# FOC_Drive.net
KiCad netlist of a schematic drawn in Altium Designer
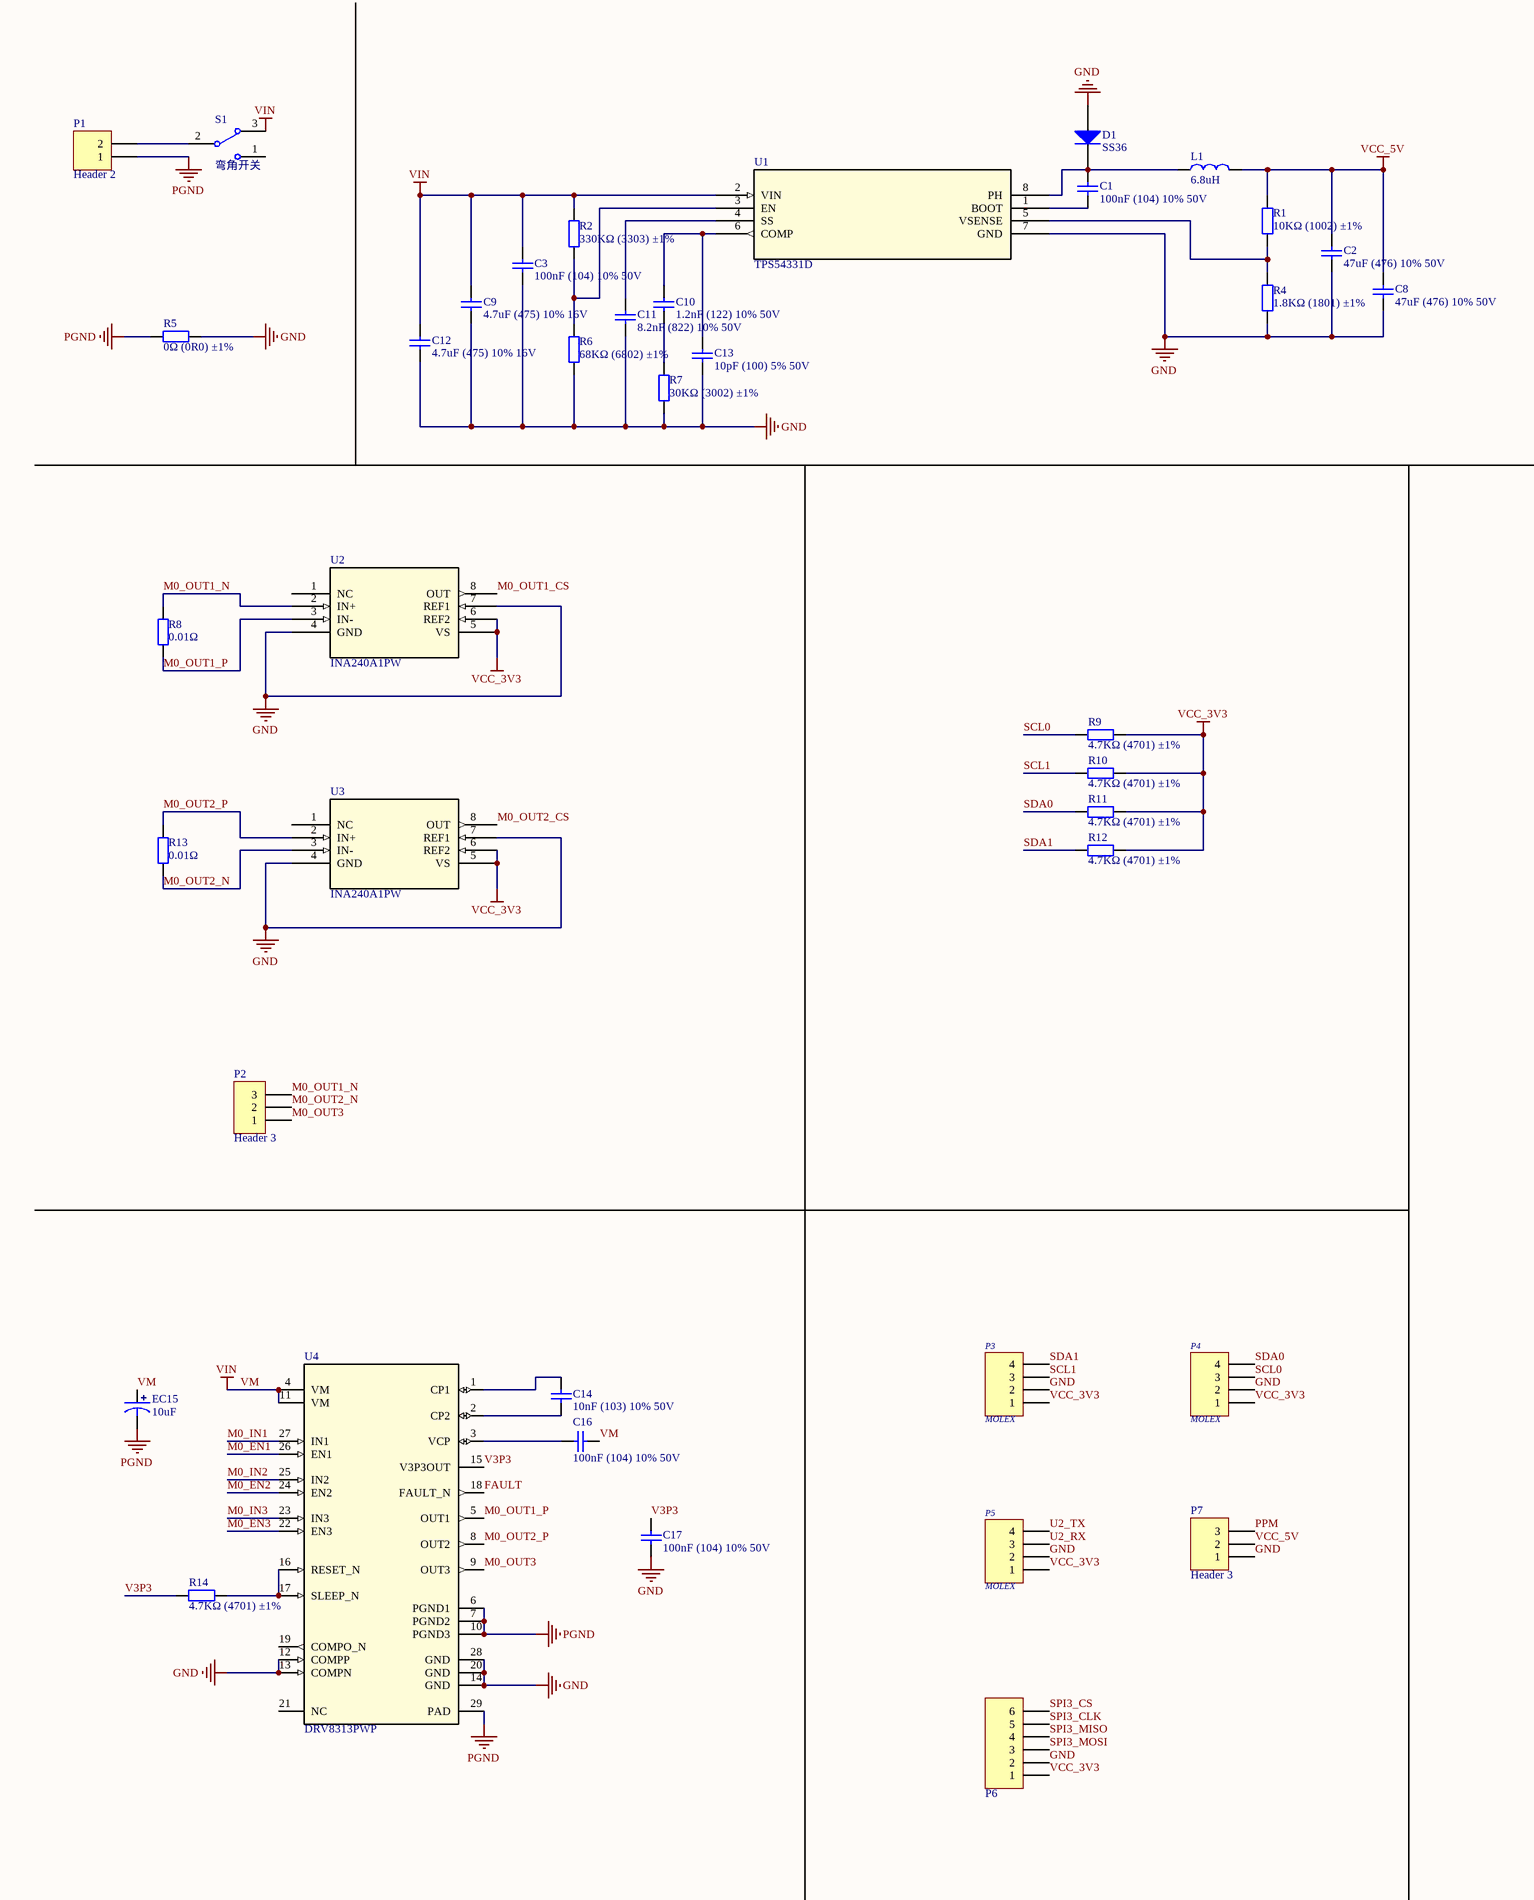
[diagram p0: FOC Drive.SchDoc, left]
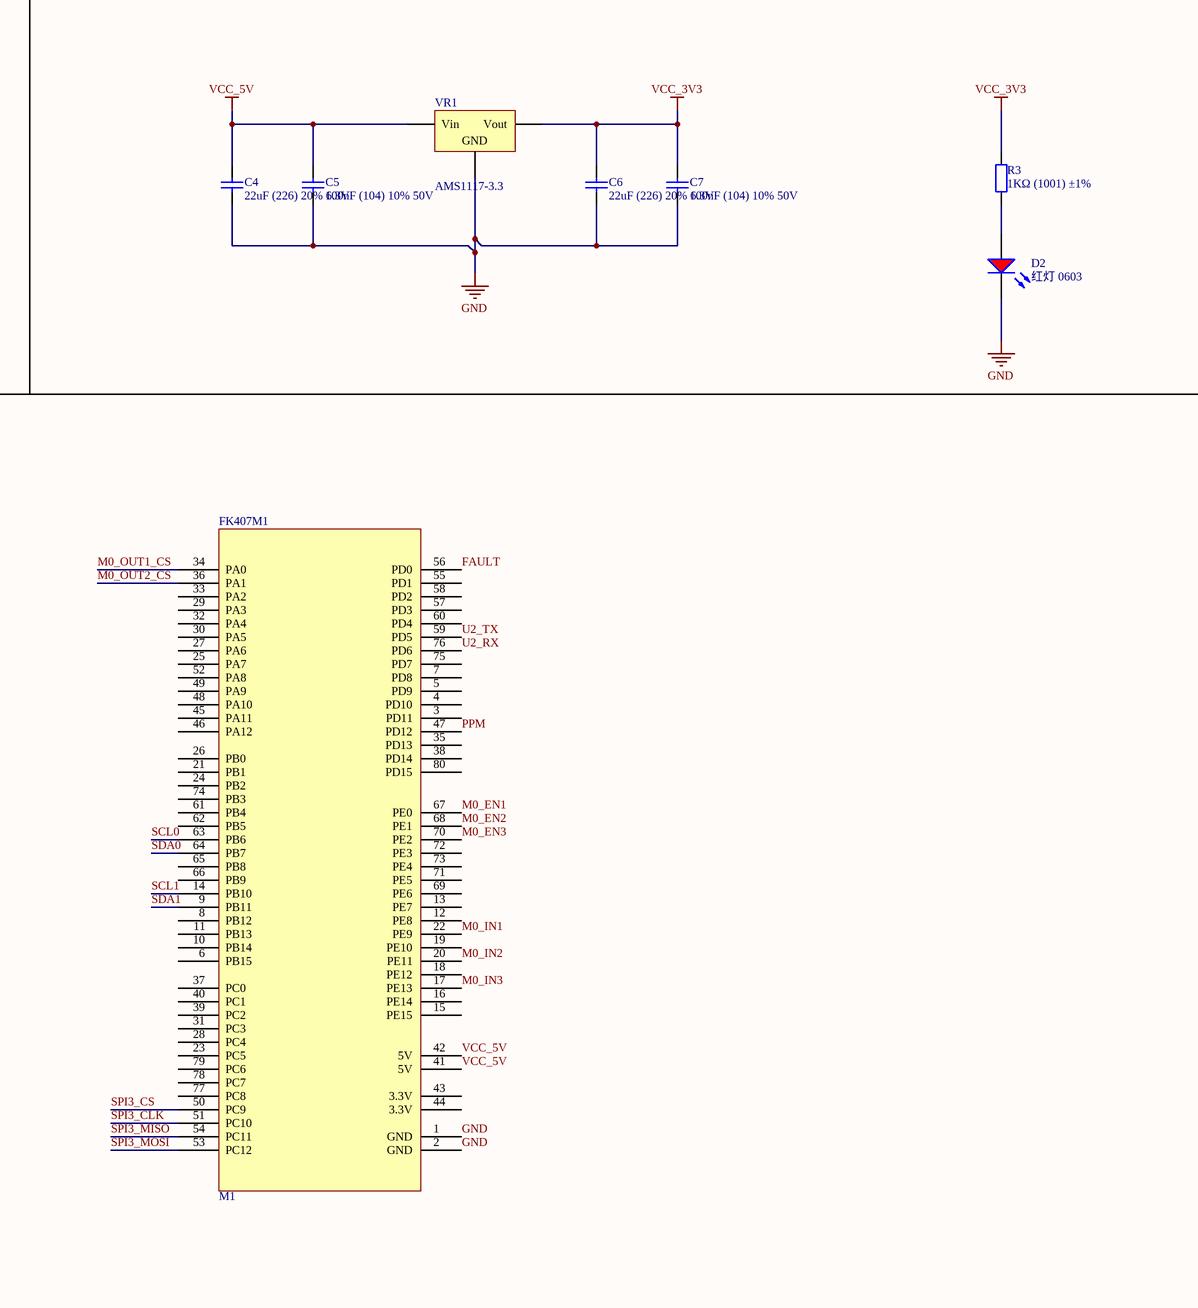
[diagram p1: FOC Drive.SchDoc, right]

(export (version "E")
  (design (tool "Eeschema 10.0.6"))
  (components
    (comp (ref "C1")
      (value "100nF (104) 10% 50V")
      (footprint "0603_C")
      (description "贴片电容")
      (libsource (lib "Miscellaneous Devices LC") (part "0603 100nF (104) 10% 50V"))
    )
    (comp (ref "C2")
      (value "47uF (476) 10% 50V")
      (footprint "0603_C")
      (description "贴片电容")
      (libsource (lib "Miscellaneous Devices LC") (part "0603 47nF (473) 10% 50V"))
    )
    (comp (ref "C3")
      (value "100nF (104) 10% 50V")
      (footprint "0603_C")
      (description "贴片电容")
      (libsource (lib "Miscellaneous Devices LC") (part "0603 100nF (104) 10% 50V"))
    )
    (comp (ref "C4")
      (value "22uF (226) 20% 6.3V")
      (footprint "0603_C")
      (description "贴片电容")
      (libsource (lib "Miscellaneous Devices LC") (part "0603 22uF (226) 20% 6.3V"))
    )
    (comp (ref "C5")
      (value "100nF (104) 10% 50V")
      (footprint "0603_C")
      (description "贴片电容")
      (libsource (lib "Miscellaneous Devices LC") (part "0603 100nF (104) 10% 50V"))
    )
    (comp (ref "C6")
      (value "22uF (226) 20% 6.3V")
      (footprint "0603_C")
      (description "贴片电容")
      (libsource (lib "Miscellaneous Devices LC") (part "0603 22uF (226) 20% 6.3V"))
    )
    (comp (ref "C7")
      (value "100nF (104) 10% 50V")
      (footprint "0603_C")
      (description "贴片电容")
      (libsource (lib "Miscellaneous Devices LC") (part "0603 100nF (104) 10% 50V"))
    )
    (comp (ref "C8")
      (value "47uF (476) 10% 50V")
      (footprint "0603_C")
      (description "贴片电容")
      (libsource (lib "Miscellaneous Devices LC") (part "0603 47nF (473) 10% 50V"))
    )
    (comp (ref "C9")
      (value "4.7uF (475) 10% 16V")
      (footprint "0603_C")
      (description "贴片电容")
      (libsource (lib "Miscellaneous Devices LC") (part "0603 4.7uF (475) 10% 16V"))
    )
    (comp (ref "C10")
      (value "1.2nF (122) 10% 50V")
      (footprint "0603_C")
      (description "贴片电容")
      (libsource (lib "Miscellaneous Devices LC") (part "0603 1.2nF (122) 10% 50V"))
    )
    (comp (ref "C11")
      (value "8.2nF (822) 10% 50V")
      (footprint "0603_C")
      (description "贴片电容")
      (libsource (lib "Miscellaneous Devices LC") (part "0603 8.2nF (822) 10% 50V"))
    )
    (comp (ref "C12")
      (value "4.7uF (475) 10% 16V")
      (footprint "0603_C")
      (description "贴片电容")
      (libsource (lib "Miscellaneous Devices LC") (part "0603 4.7uF (475) 10% 16V"))
    )
    (comp (ref "C13")
      (value "10pF (100) 5% 50V")
      (footprint "0603_C")
      (description "贴片电容")
      (libsource (lib "Miscellaneous Devices LC") (part "0603 10pF (100) 5% 50V"))
    )
    (comp (ref "C14")
      (value "10nF (103) 10% 50V")
      (footprint "0603_C")
      (description "贴片电容")
      (libsource (lib "Miscellaneous Devices LC") (part "0603 10nF (103) 10% 50V"))
    )
    (comp (ref "C16")
      (value "100nF (104) 10% 50V")
      (footprint "0603_C")
      (description "贴片电容")
      (libsource (lib "Miscellaneous Devices LC") (part "0603 100nF (104) 10% 50V"))
    )
    (comp (ref "C17")
      (value "100nF (104) 10% 50V")
      (footprint "0603_C")
      (description "贴片电容")
      (libsource (lib "Miscellaneous Devices LC") (part "0603 100nF (104) 10% 50V"))
    )
    (comp (ref "D1")
      (value "SS36")
      (footprint "SMA(DO-214AC)_S5")
      (description "二极管")
      (libsource (lib "Miscellaneous Customized Items") (part "SMA(DO-214AC) US1M"))
    )
    (comp (ref "D2")
      (value "红灯 0603")
      (footprint "0603_LED_S1")
      (description "发光二极管")
      (libsource (lib "Miscellaneous Devices LC") (part "0603 红灯"))
    )
    (comp (ref "EC15")
      (value "10uF")
      (footprint "SMD-EC5.0X5.3X5.4")
      (description "贴片电解电容")
      (libsource (lib "电容") (part "SMD_ECAP"))
    )
    (comp (ref "FK407M1")
      (value "M1")
      (footprint "FK407M1")
      (libsource (lib "Miscellaneous Customized Items") (part "FK407M1"))
    )
    (comp (ref "L1")
      (value "6.8uH")
      (footprint "IND-SMD_L5.0-W5.0_SWPA5040S")
      (description "5040")
      (libsource (lib "Miscellaneous Customized Items") (part "L"))
    )
    (comp (ref "P1")
      (value "Header 2")
      (footprint "KF127-2P-5mm")
      (description "Header, 2-Pin")
      (fields (field (name "PUBLISHER") "Altium Limited"))
      (libsource (lib "Miscellaneous Customized Items") (part "Header 2 5mm"))
    )
    (comp (ref "P2")
      (value "Header 3")
      (footprint "KF127-3P-5mm")
      (description "Header, 3-Pin")
      (fields (field (name "PUBLISHER") "Altium Limited"))
      (libsource (lib "Miscellaneous Customized Items") (part "Header 3"))
    )
    (comp (ref "P3")
      (value "MOLEX")
      (footprint "SH1.0-4P-L")
      (fields (field (name "PUBLISHER") "Altium Limited"))
      (libsource (lib "TM4C_Series") (part "SH_4P"))
    )
    (comp (ref "P4")
      (value "MOLEX")
      (footprint "SH1.0-4P-L")
      (fields (field (name "PUBLISHER") "Altium Limited"))
      (libsource (lib "TM4C_Series") (part "SH_4P"))
    )
    (comp (ref "P5")
      (value "MOLEX")
      (footprint "SH1.0-4P-L")
      (fields (field (name "PUBLISHER") "Altium Limited"))
      (libsource (lib "TM4C_Series") (part "SH_4P"))
    )
    (comp (ref "P6")
      (value "SH_6P")
      (footprint "SH1.0-6P-L")
      (description "Header, 6-Pin")
      (fields (field (name "PUBLISHER") "Altium Limited"))
      (libsource (lib "TM4C_Series") (part "SH_6P"))
    )
    (comp (ref "P7")
      (value "Header 3")
      (footprint "HDR1X3")
      (description "Header, 3-Pin")
      (fields (field (name "PUBLISHER") "Altium Limited"))
      (libsource (lib "Miscellaneous Connectors") (part "Header 3"))
    )
    (comp (ref "R1")
      (value "10KΩ (1002) ±1%")
      (footprint "0603_R")
      (description "贴片电阻")
      (libsource (lib "Miscellaneous Devices LC") (part "0603 10KΩ (1002) 1%"))
    )
    (comp (ref "R2")
      (value "330KΩ (3303) ±1%")
      (footprint "0603_R")
      (description "贴片电阻")
      (libsource (lib "Miscellaneous Devices LC") (part "0603 330KΩ (3303) 1%"))
    )
    (comp (ref "R3")
      (value "1KΩ (1001) ±1%")
      (footprint "0603_R")
      (description "贴片电阻")
      (libsource (lib "Miscellaneous Devices LC") (part "0603 1KΩ (1001) 1%"))
    )
    (comp (ref "R4")
      (value "1.8KΩ (1801) ±1%")
      (footprint "0603_R")
      (description "贴片电阻")
      (libsource (lib "Miscellaneous Devices LC") (part "0603 1.8KΩ (1801) 1%"))
    )
    (comp (ref "R5")
      (value "0Ω (0R0) ±1%")
      (footprint "0805_R")
      (description "贴片电阻")
      (libsource (lib "Miscellaneous Devices LC") (part "0805 0Ω (0R0) 1%"))
    )
    (comp (ref "R6")
      (value "68KΩ (6802) ±1%")
      (footprint "0603_R")
      (description "贴片电阻")
      (libsource (lib "Miscellaneous Devices LC") (part "0603 68KΩ (6802) 1%"))
    )
    (comp (ref "R7")
      (value "30KΩ (3002) ±1%")
      (footprint "0603_R")
      (description "贴片电阻")
      (libsource (lib "Miscellaneous Devices LC") (part "0603 30KΩ (3002) 1%"))
    )
    (comp (ref "R8")
      (value "0.01Ω")
      (footprint "1206_R")
      (description "贴片电阻")
      (libsource (lib "Miscellaneous Devices LC") (part "1206 0Ω (0R0) 1%"))
    )
    (comp (ref "R9")
      (value "4.7KΩ (4701) ±1%")
      (footprint "0603_R")
      (description "贴片电阻")
      (libsource (lib "Miscellaneous Devices LC") (part "0603 4.7KΩ (4701) 1%"))
    )
    (comp (ref "R10")
      (value "4.7KΩ (4701) ±1%")
      (footprint "0603_R")
      (description "贴片电阻")
      (libsource (lib "Miscellaneous Devices LC") (part "0603 4.7KΩ (4701) 1%"))
    )
    (comp (ref "R11")
      (value "4.7KΩ (4701) ±1%")
      (footprint "0603_R")
      (description "贴片电阻")
      (libsource (lib "Miscellaneous Devices LC") (part "0603 4.7KΩ (4701) 1%"))
    )
    (comp (ref "R12")
      (value "4.7KΩ (4701) ±1%")
      (footprint "0603_R")
      (description "贴片电阻")
      (libsource (lib "Miscellaneous Devices LC") (part "0603 4.7KΩ (4701) 1%"))
    )
    (comp (ref "R13")
      (value "0.01Ω")
      (footprint "1206_R")
      (description "贴片电阻")
      (libsource (lib "Miscellaneous Devices LC") (part "1206 0Ω (0R0) 1%"))
    )
    (comp (ref "R14")
      (value "4.7KΩ (4701) ±1%")
      (footprint "0603_R")
      (description "贴片电阻")
      (libsource (lib "Miscellaneous Devices LC") (part "0603 4.7KΩ (4701) 1%"))
    )
    (comp (ref "S1")
      (value "弯角开关")
      (footprint "SS-12F23")
      (libsource (lib "Miscellaneous Customized Items") (part "SS-12F23"))
    )
    (comp (ref "U1")
      (value "TPS54331D")
      (footprint "D8-M")
      (description "No Description Available")
      (fields (field (name "COPYRIGHT") "Copyright (C) 2022 Ultra Librarian. All rights reserved."))
      (libsource (lib "Miscellaneous Customized Items") (part "TPS54331D"))
    )
    (comp (ref "U2")
      (value "INA240A1PW")
      (footprint "PW0008A_N_TEX")
      (description "No Description Available")
      (fields (field (name "COPYRIGHT") "Copyright (C) 2022 Ultra Librarian. All rights reserved."))
      (libsource (lib "Miscellaneous Customized Items") (part "INA240A1PW"))
    )
    (comp (ref "U3")
      (value "INA240A1PW")
      (footprint "PW0008A_N_TEX")
      (description "No Description Available")
      (fields (field (name "COPYRIGHT") "Copyright (C) 2022 Ultra Librarian. All rights reserved."))
      (libsource (lib "Miscellaneous Customized Items") (part "INA240A1PW"))
    )
    (comp (ref "U4")
      (value "DRV8313PWP")
      (footprint "PWP0028F_N")
      (description "No Description Available")
      (fields (field (name "COPYRIGHT") "Copyright (C) 2022 Ultra Librarian. All rights reserved."))
      (libsource (lib "Miscellaneous Customized Items") (part "DRV8313PWP"))
    )
    (comp (ref "VR1")
      (value "AMS1117-3.3")
      (footprint "SOT-223")
      (description "低压差线性稳压(LDO)")
      (libsource (lib "Miscellaneous Devices LC") (part "SOT-223 AMS1117-3.3"))
    )
  )
  (nets
    (net (code "1") (name "/FAULT") (class "Default")
      (node (ref "FK407M1") (pin "56") (pinfunction "PD0_56") (pintype "passive"))
      (node (ref "U4") (pin "18") (pinfunction "FAULT_N_18") (pintype "output"))
    )
    (net (code "2") (name "/M0_EN1") (class "Default")
      (node (ref "FK407M1") (pin "67") (pinfunction "PE0_67") (pintype "passive"))
      (node (ref "U4") (pin "26") (pinfunction "EN1_26") (pintype "input"))
    )
    (net (code "3") (name "/M0_EN2") (class "Default")
      (node (ref "FK407M1") (pin "68") (pinfunction "PE1_68") (pintype "passive"))
      (node (ref "U4") (pin "24") (pinfunction "EN2_24") (pintype "input"))
    )
    (net (code "4") (name "/M0_EN3") (class "Default")
      (node (ref "FK407M1") (pin "70") (pinfunction "PE2_70") (pintype "passive"))
      (node (ref "U4") (pin "22") (pinfunction "EN3_22") (pintype "input"))
    )
    (net (code "5") (name "/M0_IN1") (class "Default")
      (node (ref "FK407M1") (pin "22") (pinfunction "PE9_22") (pintype "passive"))
      (node (ref "U4") (pin "27") (pinfunction "IN1_27") (pintype "input"))
    )
    (net (code "6") (name "/M0_IN2") (class "Default")
      (node (ref "FK407M1") (pin "20") (pinfunction "PE11_20") (pintype "passive"))
      (node (ref "U4") (pin "25") (pinfunction "IN2_25") (pintype "input"))
    )
    (net (code "7") (name "/M0_IN3") (class "Default")
      (node (ref "FK407M1") (pin "17") (pinfunction "PE13_17") (pintype "passive"))
      (node (ref "U4") (pin "23") (pinfunction "IN3_23") (pintype "input"))
    )
    (net (code "8") (name "/M0_OUT1_CS") (class "Default")
      (node (ref "FK407M1") (pin "34") (pinfunction "PA0_34") (pintype "passive"))
      (node (ref "U2") (pin "8") (pinfunction "OUT_8") (pintype "output"))
    )
    (net (code "9") (name "/M0_OUT1_N") (class "Default")
      (node (ref "P2") (pin "3") (pinfunction "3_3") (pintype "passive"))
      (node (ref "R8") (pin "2") (pinfunction "2_2") (pintype "passive"))
      (node (ref "U2") (pin "2") (pinfunction "IN+_2") (pintype "input"))
    )
    (net (code "10") (name "/M0_OUT1_P") (class "Default")
      (node (ref "R8") (pin "1") (pinfunction "1_1") (pintype "passive"))
      (node (ref "U2") (pin "3") (pinfunction "IN-_3") (pintype "input"))
      (node (ref "U4") (pin "5") (pinfunction "OUT1_5") (pintype "output"))
    )
    (net (code "11") (name "/M0_OUT2_CS") (class "Default")
      (node (ref "FK407M1") (pin "36") (pinfunction "PA1_36") (pintype "passive"))
      (node (ref "U3") (pin "8") (pinfunction "OUT_8") (pintype "output"))
    )
    (net (code "12") (name "/M0_OUT2_N") (class "Default")
      (node (ref "P2") (pin "2") (pinfunction "2_2") (pintype "passive"))
      (node (ref "R13") (pin "1") (pinfunction "1_1") (pintype "passive"))
      (node (ref "U3") (pin "3") (pinfunction "IN-_3") (pintype "input"))
    )
    (net (code "13") (name "/M0_OUT2_P") (class "Default")
      (node (ref "R13") (pin "2") (pinfunction "2_2") (pintype "passive"))
      (node (ref "U3") (pin "2") (pinfunction "IN+_2") (pintype "input"))
      (node (ref "U4") (pin "8") (pinfunction "OUT2_8") (pintype "output"))
    )
    (net (code "14") (name "/M0_OUT3") (class "Default")
      (node (ref "P2") (pin "1") (pinfunction "1_1") (pintype "passive"))
      (node (ref "U4") (pin "9") (pinfunction "OUT3_9") (pintype "output"))
    )
    (net (code "15") (name "/PPM") (class "Default")
      (node (ref "FK407M1") (pin "47") (pinfunction "PD12_47") (pintype "passive"))
      (node (ref "P7") (pin "3") (pinfunction "3_3") (pintype "passive"))
    )
    (net (code "16") (name "/SCL0") (class "Default")
      (node (ref "FK407M1") (pin "63") (pinfunction "PB6_63") (pintype "passive"))
      (node (ref "P4") (pin "3") (pinfunction "3_3") (pintype "passive"))
      (node (ref "R9") (pin "1") (pinfunction "1_1") (pintype "passive"))
    )
    (net (code "17") (name "/SCL1") (class "Default")
      (node (ref "FK407M1") (pin "14") (pinfunction "PB10_14") (pintype "passive"))
      (node (ref "P3") (pin "3") (pinfunction "3_3") (pintype "passive"))
      (node (ref "R10") (pin "1") (pinfunction "1_1") (pintype "passive"))
    )
    (net (code "18") (name "/SDA0") (class "Default")
      (node (ref "FK407M1") (pin "64") (pinfunction "PB7_64") (pintype "passive"))
      (node (ref "P4") (pin "4") (pinfunction "4_4") (pintype "passive"))
      (node (ref "R11") (pin "1") (pinfunction "1_1") (pintype "passive"))
    )
    (net (code "19") (name "/SDA1") (class "Default")
      (node (ref "FK407M1") (pin "9") (pinfunction "PB11_9") (pintype "passive"))
      (node (ref "P3") (pin "4") (pinfunction "4_4") (pintype "passive"))
      (node (ref "R12") (pin "1") (pinfunction "1_1") (pintype "passive"))
    )
    (net (code "20") (name "/SPI3_CLK") (class "Default")
      (node (ref "FK407M1") (pin "51") (pinfunction "PC10_51") (pintype "passive"))
      (node (ref "P6") (pin "5") (pinfunction "5_5") (pintype "passive"))
    )
    (net (code "21") (name "/SPI3_CS") (class "Default")
      (node (ref "FK407M1") (pin "50") (pinfunction "PC9_50") (pintype "passive"))
      (node (ref "P6") (pin "6") (pinfunction "6_6") (pintype "passive"))
    )
    (net (code "22") (name "/SPI3_MISO") (class "Default")
      (node (ref "FK407M1") (pin "54") (pinfunction "PC11_54") (pintype "passive"))
      (node (ref "P6") (pin "4") (pinfunction "4_4") (pintype "passive"))
    )
    (net (code "23") (name "/SPI3_MOSI") (class "Default")
      (node (ref "FK407M1") (pin "53") (pinfunction "PC12_53") (pintype "passive"))
      (node (ref "P6") (pin "3") (pinfunction "3_3") (pintype "passive"))
    )
    (net (code "24") (name "/U2_RX") (class "Default")
      (node (ref "FK407M1") (pin "76") (pinfunction "PD6_76") (pintype "passive"))
      (node (ref "P5") (pin "3") (pinfunction "3_3") (pintype "passive"))
    )
    (net (code "25") (name "/U2_TX") (class "Default")
      (node (ref "FK407M1") (pin "59") (pinfunction "PD5_59") (pintype "passive"))
      (node (ref "P5") (pin "4") (pinfunction "4_4") (pintype "passive"))
    )
    (net (code "26") (name "/V3P3") (class "Default")
      (node (ref "C17") (pin "2") (pinfunction "2_2") (pintype "passive"))
      (node (ref "R14") (pin "1") (pinfunction "1_1") (pintype "passive"))
      (node (ref "U4") (pin "15") (pinfunction "V3P3OUT_15") (pintype "power_in"))
    )
    (net (code "27") (name "GND") (class "Default")
      (node (ref "C11") (pin "1") (pinfunction "1_1") (pintype "passive"))
      (node (ref "C12") (pin "1") (pinfunction "1_1") (pintype "passive"))
      (node (ref "C13") (pin "1") (pinfunction "1_1") (pintype "passive"))
      (node (ref "C17") (pin "1") (pinfunction "1_1") (pintype "passive"))
      (node (ref "C2") (pin "1") (pinfunction "1_1") (pintype "passive"))
      (node (ref "C3") (pin "1") (pinfunction "1_1") (pintype "passive"))
      (node (ref "C4") (pin "1") (pinfunction "1_1") (pintype "passive"))
      (node (ref "C5") (pin "1") (pinfunction "1_1") (pintype "passive"))
      (node (ref "C6") (pin "1") (pinfunction "1_1") (pintype "passive"))
      (node (ref "C7") (pin "1") (pinfunction "1_1") (pintype "passive"))
      (node (ref "C8") (pin "1") (pinfunction "1_1") (pintype "passive"))
      (node (ref "C9") (pin "1") (pinfunction "1_1") (pintype "passive"))
      (node (ref "D1") (pin "1") (pinfunction "A_1") (pintype "passive"))
      (node (ref "D2") (pin "K") (pinfunction "K_K") (pintype "passive"))
      (node (ref "FK407M1") (pin "1") (pinfunction "GND_1") (pintype "passive"))
      (node (ref "FK407M1") (pin "2") (pinfunction "GND_2") (pintype "passive"))
      (node (ref "P3") (pin "2") (pinfunction "2_2") (pintype "passive"))
      (node (ref "P4") (pin "2") (pinfunction "2_2") (pintype "passive"))
      (node (ref "P5") (pin "2") (pinfunction "2_2") (pintype "passive"))
      (node (ref "P6") (pin "2") (pinfunction "2_2") (pintype "passive"))
      (node (ref "P7") (pin "1") (pinfunction "1_1") (pintype "passive"))
      (node (ref "R4") (pin "1") (pinfunction "1_1") (pintype "passive"))
      (node (ref "R5") (pin "2") (pinfunction "2_2") (pintype "passive"))
      (node (ref "R6") (pin "1") (pinfunction "1_1") (pintype "passive"))
      (node (ref "R7") (pin "1") (pinfunction "1_1") (pintype "passive"))
      (node (ref "U1") (pin "7") (pinfunction "GND_7") (pintype "power_in"))
      (node (ref "U2") (pin "4") (pinfunction "GND_4") (pintype "power_in"))
      (node (ref "U2") (pin "7") (pinfunction "REF1_7") (pintype "input"))
      (node (ref "U3") (pin "4") (pinfunction "GND_4") (pintype "power_in"))
      (node (ref "U3") (pin "7") (pinfunction "REF1_7") (pintype "input"))
      (node (ref "U4") (pin "12") (pinfunction "COMPP_12") (pintype "input"))
      (node (ref "U4") (pin "13") (pinfunction "COMPN_13") (pintype "input"))
      (node (ref "U4") (pin "14") (pinfunction "GND_14") (pintype "power_in"))
      (node (ref "U4") (pin "20") (pinfunction "GND_20") (pintype "power_in"))
      (node (ref "U4") (pin "28") (pinfunction "GND_28") (pintype "power_in"))
      (node (ref "VR1") (pin "1") (pinfunction "GND_1") (pintype "passive"))
    )
    (net (code "28") (name "Net-(C10-Pad1)") (class "Default")
      (node (ref "C10") (pin "1") (pinfunction "1_1") (pintype "passive"))
      (node (ref "R7") (pin "2") (pinfunction "2_2") (pintype "passive"))
    )
    (net (code "29") (name "Net-(D1-K)") (class "Default")
      (node (ref "C1") (pin "2") (pinfunction "2_2") (pintype "passive"))
      (node (ref "D1") (pin "2") (pinfunction "K_2") (pintype "passive"))
      (node (ref "L1") (pin "2") (pinfunction "2_2") (pintype "passive"))
      (node (ref "U1") (pin "8") (pinfunction "PH_8") (pintype "power_in"))
    )
    (net (code "30") (name "Net-(D2-PadA)") (class "Default")
      (node (ref "D2") (pin "A") (pinfunction "A_A") (pintype "passive"))
      (node (ref "R3") (pin "1") (pinfunction "1_1") (pintype "passive"))
    )
    (net (code "31") (name "Net-(P1-Pad2)") (class "Default")
      (node (ref "P1") (pin "2") (pinfunction "2_2") (pintype "passive"))
      (node (ref "S1") (pin "2") (pinfunction "2_2") (pintype "passive"))
    )
    (net (code "32") (name "Net-(U1-BOOT)") (class "Default")
      (node (ref "C1") (pin "1") (pinfunction "1_1") (pintype "passive"))
      (node (ref "U1") (pin "1") (pinfunction "BOOT_1") (pintype "passive"))
    )
    (net (code "33") (name "Net-(U1-COMP)") (class "Default")
      (node (ref "C10") (pin "2") (pinfunction "2_2") (pintype "passive"))
      (node (ref "C13") (pin "2") (pinfunction "2_2") (pintype "passive"))
      (node (ref "U1") (pin "6") (pinfunction "COMP_6") (pintype "output"))
    )
    (net (code "34") (name "Net-(U1-EN)") (class "Default")
      (node (ref "R2") (pin "1") (pinfunction "1_1") (pintype "passive"))
      (node (ref "R6") (pin "2") (pinfunction "2_2") (pintype "passive"))
      (node (ref "U1") (pin "3") (pinfunction "EN_3") (pintype "passive"))
    )
    (net (code "35") (name "Net-(U1-SS)") (class "Default")
      (node (ref "C11") (pin "2") (pinfunction "2_2") (pintype "passive"))
      (node (ref "U1") (pin "4") (pinfunction "SS_4") (pintype "passive"))
    )
    (net (code "36") (name "Net-(U1-VSENSE)") (class "Default")
      (node (ref "R1") (pin "1") (pinfunction "1_1") (pintype "passive"))
      (node (ref "R4") (pin "2") (pinfunction "2_2") (pintype "passive"))
      (node (ref "U1") (pin "5") (pinfunction "VSENSE_5") (pintype "passive"))
    )
    (net (code "37") (name "Net-(U4-CP1)") (class "Default")
      (node (ref "C14") (pin "2") (pinfunction "2_2") (pintype "passive"))
      (node (ref "U4") (pin "1") (pinfunction "CP1_1") (pintype "bidirectional"))
    )
    (net (code "38") (name "Net-(U4-CP2)") (class "Default")
      (node (ref "C14") (pin "1") (pinfunction "1_1") (pintype "passive"))
      (node (ref "U4") (pin "2") (pinfunction "CP2_2") (pintype "bidirectional"))
    )
    (net (code "39") (name "Net-(U4-RESET_N)") (class "Default")
      (node (ref "R14") (pin "2") (pinfunction "2_2") (pintype "passive"))
      (node (ref "U4") (pin "16") (pinfunction "RESET_N_16") (pintype "input"))
      (node (ref "U4") (pin "17") (pinfunction "SLEEP_N_17") (pintype "input"))
    )
    (net (code "40") (name "Net-(U4-VCP)") (class "Default")
      (node (ref "C16") (pin "2") (pinfunction "2_2") (pintype "passive"))
      (node (ref "U4") (pin "3") (pinfunction "VCP_3") (pintype "bidirectional"))
    )
    (net (code "41") (name "PGND") (class "Default")
      (node (ref "EC15") (pin "2") (pinfunction "2_2") (pintype "passive"))
      (node (ref "P1") (pin "1") (pinfunction "1_1") (pintype "passive"))
      (node (ref "R5") (pin "1") (pinfunction "1_1") (pintype "passive"))
      (node (ref "U4") (pin "10") (pinfunction "PGND3_10") (pintype "power_in"))
      (node (ref "U4") (pin "29") (pinfunction "PAD_29") (pintype "power_in"))
      (node (ref "U4") (pin "6") (pinfunction "PGND1_6") (pintype "power_in"))
      (node (ref "U4") (pin "7") (pinfunction "PGND2_7") (pintype "power_in"))
    )
    (net (code "42") (name "VCC_3V3") (class "Default")
      (node (ref "C6") (pin "2") (pinfunction "2_2") (pintype "passive"))
      (node (ref "C7") (pin "2") (pinfunction "2_2") (pintype "passive"))
      (node (ref "P3") (pin "1") (pinfunction "1_1") (pintype "passive"))
      (node (ref "P4") (pin "1") (pinfunction "1_1") (pintype "passive"))
      (node (ref "P5") (pin "1") (pinfunction "1_1") (pintype "passive"))
      (node (ref "P6") (pin "1") (pinfunction "1_1") (pintype "passive"))
      (node (ref "R10") (pin "2") (pinfunction "2_2") (pintype "passive"))
      (node (ref "R11") (pin "2") (pinfunction "2_2") (pintype "passive"))
      (node (ref "R12") (pin "2") (pinfunction "2_2") (pintype "passive"))
      (node (ref "R3") (pin "2") (pinfunction "2_2") (pintype "passive"))
      (node (ref "R9") (pin "2") (pinfunction "2_2") (pintype "passive"))
      (node (ref "U2") (pin "5") (pinfunction "VS_5") (pintype "power_in"))
      (node (ref "U2") (pin "6") (pinfunction "REF2_6") (pintype "input"))
      (node (ref "U3") (pin "5") (pinfunction "VS_5") (pintype "power_in"))
      (node (ref "U3") (pin "6") (pinfunction "REF2_6") (pintype "input"))
      (node (ref "VR1") (pin "2") (pinfunction "Vout_2") (pintype "passive"))
    )
    (net (code "43") (name "VCC_5V") (class "Default")
      (node (ref "C2") (pin "2") (pinfunction "2_2") (pintype "passive"))
      (node (ref "C4") (pin "2") (pinfunction "2_2") (pintype "passive"))
      (node (ref "C5") (pin "2") (pinfunction "2_2") (pintype "passive"))
      (node (ref "C8") (pin "2") (pinfunction "2_2") (pintype "passive"))
      (node (ref "FK407M1") (pin "41") (pinfunction "5V_41") (pintype "passive"))
      (node (ref "FK407M1") (pin "42") (pinfunction "5V_42") (pintype "passive"))
      (node (ref "L1") (pin "1") (pinfunction "1_1") (pintype "passive"))
      (node (ref "P7") (pin "2") (pinfunction "2_2") (pintype "passive"))
      (node (ref "R1") (pin "2") (pinfunction "2_2") (pintype "passive"))
      (node (ref "VR1") (pin "3") (pinfunction "Vin_3") (pintype "passive"))
    )
    (net (code "44") (name "VIN") (class "Default")
      (node (ref "C12") (pin "2") (pinfunction "2_2") (pintype "passive"))
      (node (ref "C16") (pin "1") (pinfunction "1_1") (pintype "passive"))
      (node (ref "C3") (pin "2") (pinfunction "2_2") (pintype "passive"))
      (node (ref "C9") (pin "2") (pinfunction "2_2") (pintype "passive"))
      (node (ref "EC15") (pin "1") (pinfunction "1_1") (pintype "passive"))
      (node (ref "R2") (pin "2") (pinfunction "2_2") (pintype "passive"))
      (node (ref "S1") (pin "3") (pinfunction "3_3") (pintype "passive"))
      (node (ref "U1") (pin "2") (pinfunction "VIN_2") (pintype "input"))
      (node (ref "U4") (pin "11") (pinfunction "VM_11") (pintype "power_in"))
      (node (ref "U4") (pin "4") (pinfunction "VM_4") (pintype "power_in"))
    )
    (net (code "45") (name "unconnected-(FK407M1-3.3V-Pad43)") (class "Default")
      (node (ref "FK407M1") (pin "43") (pinfunction "3.3V_43") (pintype "passive"))
    )
    (net (code "46") (name "unconnected-(FK407M1-3.3V-Pad44)") (class "Default")
      (node (ref "FK407M1") (pin "44") (pinfunction "3.3V_44") (pintype "passive"))
    )
    (net (code "47") (name "unconnected-(FK407M1-PA2-Pad33)") (class "Default")
      (node (ref "FK407M1") (pin "33") (pinfunction "PA2_33") (pintype "passive"))
    )
    (net (code "48") (name "unconnected-(FK407M1-PA3-Pad29)") (class "Default")
      (node (ref "FK407M1") (pin "29") (pinfunction "PA3_29") (pintype "passive"))
    )
    (net (code "49") (name "unconnected-(FK407M1-PA4-Pad32)") (class "Default")
      (node (ref "FK407M1") (pin "32") (pinfunction "PA4_32") (pintype "passive"))
    )
    (net (code "50") (name "unconnected-(FK407M1-PA5-Pad30)") (class "Default")
      (node (ref "FK407M1") (pin "30") (pinfunction "PA5_30") (pintype "passive"))
    )
    (net (code "51") (name "unconnected-(FK407M1-PA6-Pad27)") (class "Default")
      (node (ref "FK407M1") (pin "27") (pinfunction "PA6_27") (pintype "passive"))
    )
    (net (code "52") (name "unconnected-(FK407M1-PA7-Pad25)") (class "Default")
      (node (ref "FK407M1") (pin "25") (pinfunction "PA7_25") (pintype "passive"))
    )
    (net (code "53") (name "unconnected-(FK407M1-PA8-Pad52)") (class "Default")
      (node (ref "FK407M1") (pin "52") (pinfunction "PA8_52") (pintype "passive"))
    )
    (net (code "54") (name "unconnected-(FK407M1-PA9-Pad49)") (class "Default")
      (node (ref "FK407M1") (pin "49") (pinfunction "PA9_49") (pintype "passive"))
    )
    (net (code "55") (name "unconnected-(FK407M1-PA10-Pad48)") (class "Default")
      (node (ref "FK407M1") (pin "48") (pinfunction "PA10_48") (pintype "passive"))
    )
    (net (code "56") (name "unconnected-(FK407M1-PA11-Pad45)") (class "Default")
      (node (ref "FK407M1") (pin "45") (pinfunction "PA11_45") (pintype "passive"))
    )
    (net (code "57") (name "unconnected-(FK407M1-PA12-Pad46)") (class "Default")
      (node (ref "FK407M1") (pin "46") (pinfunction "PA12_46") (pintype "passive"))
    )
    (net (code "58") (name "unconnected-(FK407M1-PB0-Pad26)") (class "Default")
      (node (ref "FK407M1") (pin "26") (pinfunction "PB0_26") (pintype "passive"))
    )
    (net (code "59") (name "unconnected-(FK407M1-PB1-Pad21)") (class "Default")
      (node (ref "FK407M1") (pin "21") (pinfunction "PB1_21") (pintype "passive"))
    )
    (net (code "60") (name "unconnected-(FK407M1-PB2-Pad24)") (class "Default")
      (node (ref "FK407M1") (pin "24") (pinfunction "PB2_24") (pintype "passive"))
    )
    (net (code "61") (name "unconnected-(FK407M1-PB3-Pad74)") (class "Default")
      (node (ref "FK407M1") (pin "74") (pinfunction "PB3_74") (pintype "passive"))
    )
    (net (code "62") (name "unconnected-(FK407M1-PB4-Pad61)") (class "Default")
      (node (ref "FK407M1") (pin "61") (pinfunction "PB4_61") (pintype "passive"))
    )
    (net (code "63") (name "unconnected-(FK407M1-PB5-Pad62)") (class "Default")
      (node (ref "FK407M1") (pin "62") (pinfunction "PB5_62") (pintype "passive"))
    )
    (net (code "64") (name "unconnected-(FK407M1-PB8-Pad65)") (class "Default")
      (node (ref "FK407M1") (pin "65") (pinfunction "PB8_65") (pintype "passive"))
    )
    (net (code "65") (name "unconnected-(FK407M1-PB9-Pad66)") (class "Default")
      (node (ref "FK407M1") (pin "66") (pinfunction "PB9_66") (pintype "passive"))
    )
    (net (code "66") (name "unconnected-(FK407M1-PB12-Pad8)") (class "Default")
      (node (ref "FK407M1") (pin "8") (pinfunction "PB12_8") (pintype "passive"))
    )
    (net (code "67") (name "unconnected-(FK407M1-PB13-Pad11)") (class "Default")
      (node (ref "FK407M1") (pin "11") (pinfunction "PB13_11") (pintype "passive"))
    )
    (net (code "68") (name "unconnected-(FK407M1-PB14-Pad10)") (class "Default")
      (node (ref "FK407M1") (pin "10") (pinfunction "PB14_10") (pintype "passive"))
    )
    (net (code "69") (name "unconnected-(FK407M1-PB15-Pad6)") (class "Default")
      (node (ref "FK407M1") (pin "6") (pinfunction "PB15_6") (pintype "passive"))
    )
    (net (code "70") (name "unconnected-(FK407M1-PC0-Pad37)") (class "Default")
      (node (ref "FK407M1") (pin "37") (pinfunction "PC0_37") (pintype "passive"))
    )
    (net (code "71") (name "unconnected-(FK407M1-PC1-Pad40)") (class "Default")
      (node (ref "FK407M1") (pin "40") (pinfunction "PC1_40") (pintype "passive"))
    )
    (net (code "72") (name "unconnected-(FK407M1-PC2-Pad39)") (class "Default")
      (node (ref "FK407M1") (pin "39") (pinfunction "PC2_39") (pintype "passive"))
    )
    (net (code "73") (name "unconnected-(FK407M1-PC3-Pad31)") (class "Default")
      (node (ref "FK407M1") (pin "31") (pinfunction "PC3_31") (pintype "passive"))
    )
    (net (code "74") (name "unconnected-(FK407M1-PC4-Pad28)") (class "Default")
      (node (ref "FK407M1") (pin "28") (pinfunction "PC4_28") (pintype "passive"))
    )
    (net (code "75") (name "unconnected-(FK407M1-PC5-Pad23)") (class "Default")
      (node (ref "FK407M1") (pin "23") (pinfunction "PC5_23") (pintype "passive"))
    )
    (net (code "76") (name "unconnected-(FK407M1-PC6-Pad79)") (class "Default")
      (node (ref "FK407M1") (pin "79") (pinfunction "PC6_79") (pintype "passive"))
    )
    (net (code "77") (name "unconnected-(FK407M1-PC7-Pad78)") (class "Default")
      (node (ref "FK407M1") (pin "78") (pinfunction "PC7_78") (pintype "passive"))
    )
    (net (code "78") (name "unconnected-(FK407M1-PC8-Pad77)") (class "Default")
      (node (ref "FK407M1") (pin "77") (pinfunction "PC8_77") (pintype "passive"))
    )
    (net (code "79") (name "unconnected-(FK407M1-PD1-Pad55)") (class "Default")
      (node (ref "FK407M1") (pin "55") (pinfunction "PD1_55") (pintype "passive"))
    )
    (net (code "80") (name "unconnected-(FK407M1-PD2-Pad58)") (class "Default")
      (node (ref "FK407M1") (pin "58") (pinfunction "PD2_58") (pintype "passive"))
    )
    (net (code "81") (name "unconnected-(FK407M1-PD3-Pad57)") (class "Default")
      (node (ref "FK407M1") (pin "57") (pinfunction "PD3_57") (pintype "passive"))
    )
    (net (code "82") (name "unconnected-(FK407M1-PD4-Pad60)") (class "Default")
      (node (ref "FK407M1") (pin "60") (pinfunction "PD4_60") (pintype "passive"))
    )
    (net (code "83") (name "unconnected-(FK407M1-PD7-Pad75)") (class "Default")
      (node (ref "FK407M1") (pin "75") (pinfunction "PD7_75") (pintype "passive"))
    )
    (net (code "84") (name "unconnected-(FK407M1-PD8-Pad7)") (class "Default")
      (node (ref "FK407M1") (pin "7") (pinfunction "PD8_7") (pintype "passive"))
    )
    (net (code "85") (name "unconnected-(FK407M1-PD9-Pad5)") (class "Default")
      (node (ref "FK407M1") (pin "5") (pinfunction "PD9_5") (pintype "passive"))
    )
    (net (code "86") (name "unconnected-(FK407M1-PD10-Pad4)") (class "Default")
      (node (ref "FK407M1") (pin "4") (pinfunction "PD10_4") (pintype "passive"))
    )
    (net (code "87") (name "unconnected-(FK407M1-PD11-Pad3)") (class "Default")
      (node (ref "FK407M1") (pin "3") (pinfunction "PD11_3") (pintype "passive"))
    )
    (net (code "88") (name "unconnected-(FK407M1-PD13-Pad35)") (class "Default")
      (node (ref "FK407M1") (pin "35") (pinfunction "PD13_35") (pintype "passive"))
    )
    (net (code "89") (name "unconnected-(FK407M1-PD14-Pad38)") (class "Default")
      (node (ref "FK407M1") (pin "38") (pinfunction "PD14_38") (pintype "passive"))
    )
    (net (code "90") (name "unconnected-(FK407M1-PD15-Pad80)") (class "Default")
      (node (ref "FK407M1") (pin "80") (pinfunction "PD15_80") (pintype "passive"))
    )
    (net (code "91") (name "unconnected-(FK407M1-PE3-Pad72)") (class "Default")
      (node (ref "FK407M1") (pin "72") (pinfunction "PE3_72") (pintype "passive"))
    )
    (net (code "92") (name "unconnected-(FK407M1-PE4-Pad73)") (class "Default")
      (node (ref "FK407M1") (pin "73") (pinfunction "PE4_73") (pintype "passive"))
    )
    (net (code "93") (name "unconnected-(FK407M1-PE5-Pad71)") (class "Default")
      (node (ref "FK407M1") (pin "71") (pinfunction "PE5_71") (pintype "passive"))
    )
    (net (code "94") (name "unconnected-(FK407M1-PE6-Pad69)") (class "Default")
      (node (ref "FK407M1") (pin "69") (pinfunction "PE6_69") (pintype "passive"))
    )
    (net (code "95") (name "unconnected-(FK407M1-PE7-Pad13)") (class "Default")
      (node (ref "FK407M1") (pin "13") (pinfunction "PE7_13") (pintype "passive"))
    )
    (net (code "96") (name "unconnected-(FK407M1-PE8-Pad12)") (class "Default")
      (node (ref "FK407M1") (pin "12") (pinfunction "PE8_12") (pintype "passive"))
    )
    (net (code "97") (name "unconnected-(FK407M1-PE10-Pad19)") (class "Default")
      (node (ref "FK407M1") (pin "19") (pinfunction "PE10_19") (pintype "passive"))
    )
    (net (code "98") (name "unconnected-(FK407M1-PE12-Pad18)") (class "Default")
      (node (ref "FK407M1") (pin "18") (pinfunction "PE12_18") (pintype "passive"))
    )
    (net (code "99") (name "unconnected-(FK407M1-PE14-Pad16)") (class "Default")
      (node (ref "FK407M1") (pin "16") (pinfunction "PE14_16") (pintype "passive"))
    )
    (net (code "100") (name "unconnected-(FK407M1-PE15-Pad15)") (class "Default")
      (node (ref "FK407M1") (pin "15") (pinfunction "PE15_15") (pintype "passive"))
    )
    (net (code "101") (name "unconnected-(S1-Pad1)") (class "Default")
      (node (ref "S1") (pin "1") (pinfunction "1_1") (pintype "passive"))
    )
    (net (code "102") (name "unconnected-(U2-NC-Pad1)") (class "Default")
      (node (ref "U2") (pin "1") (pinfunction "NC_1") (pintype "passive"))
    )
    (net (code "103") (name "unconnected-(U3-NC-Pad1)") (class "Default")
      (node (ref "U3") (pin "1") (pinfunction "NC_1") (pintype "passive"))
    )
    (net (code "104") (name "unconnected-(U4-COMPO_N-Pad19)") (class "Default")
      (node (ref "U4") (pin "19") (pinfunction "COMPO_N_19") (pintype "output"))
    )
    (net (code "105") (name "unconnected-(U4-NC-Pad21)") (class "Default")
      (node (ref "U4") (pin "21") (pinfunction "NC_21") (pintype "passive"))
    )
  )
)
